# Memory.net
KiCad netlist of a schematic drawn in Altium Designer
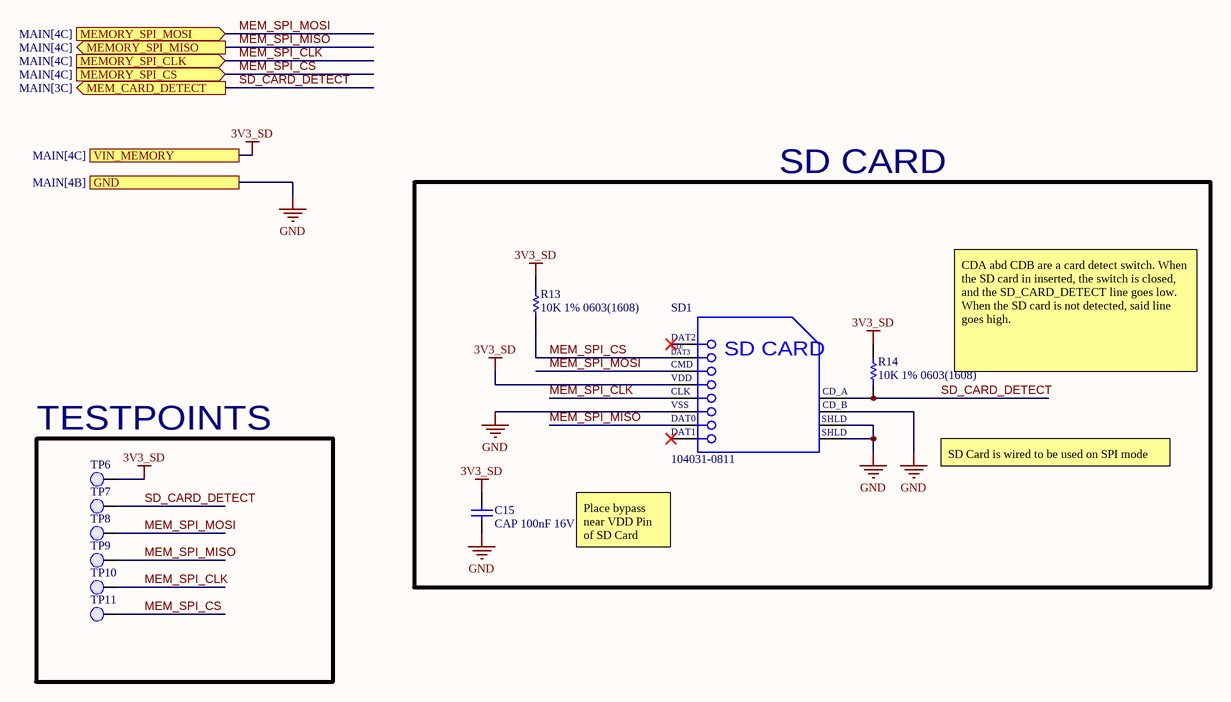
[diagram p0: Memory.SchDoc]

(export (version "E")
  (design (tool "Eeschema 10.0.6"))
  (components
    (comp (ref "C15")
      (value "CAP 100nF 16V 0603(1608)")
      (footprint "CAPC0603(1608)100_N")
      (description "CAP 100nF 16V ±10% 0603 (1608 Metric) Thickness 1mm SMD")
      (fields (field (name "TOLERANCE") "Â±10%"))
      (libsource (lib "Altium Content Vault") (part "CAP"))
    )
    (comp (ref "R13")
      (value "10K 1% 0603(1608)")
      (footprint "RESC0603(1608)_N")
      (description "10K 0.1W 1% 0603 (1608 Metric)  SMD")
      (fields (field (name "POWER") "0.1 W") (field (name "TOLERANCE") "1 %"))
      (libsource (lib "Altium Content Vault") (part "RES"))
    )
    (comp (ref "R14")
      (value "10K 1% 0603(1608)")
      (footprint "RESC0603(1608)_N")
      (description "10K 0.1W 1% 0603 (1608 Metric)  SMD")
      (fields (field (name "POWER") "0.1 W") (field (name "TOLERANCE") "1 %"))
      (libsource (lib "Altium Content Vault") (part "RES"))
    )
    (comp (ref "SD1")
      (value "104031-0811")
      (footprint "MOLX-104031-0811_V")
      (description "Micro SD Card, RA, -25 to 85 degC, 8-Pin SMD, RoHS, Tape and Reel")
      (fields (field (name "MANUFACTURER") "Molex"))
      (libsource (lib "Altium Content Vault") (part "CN-SD-8-2SW-2S"))
    )
    (comp (ref "TP6")
      (value "0.1\" Pad")
      (footprint "PCBComponent")
      (libsource (lib "Components - 12.02.20 - 18.05") (part "0.1{dblquote} Pad-A.4"))
    )
    (comp (ref "TP7")
      (value "0.1\" Pad")
      (footprint "PCBComponent")
      (libsource (lib "Components - 12.02.20 - 18.05") (part "0.1{dblquote} Pad-A.4"))
    )
    (comp (ref "TP8")
      (value "0.1\" Pad")
      (footprint "PCBComponent")
      (libsource (lib "Components - 12.02.20 - 18.05") (part "0.1{dblquote} Pad-A.4"))
    )
    (comp (ref "TP9")
      (value "0.1\" Pad")
      (footprint "PCBComponent")
      (libsource (lib "Components - 12.02.20 - 18.05") (part "0.1{dblquote} Pad-A.4"))
    )
    (comp (ref "TP10")
      (value "0.1\" Pad")
      (footprint "PCBComponent")
      (libsource (lib "Components - 12.02.20 - 18.05") (part "0.1{dblquote} Pad-A.4"))
    )
    (comp (ref "TP11")
      (value "0.1\" Pad")
      (footprint "PCBComponent")
      (libsource (lib "Components - 12.02.20 - 18.05") (part "0.1{dblquote} Pad-A.4"))
    )
  )
  (nets
    (net (code "1") (name "/MEM_SPI_CLK") (class "Default")
      (node (ref "SD1") (pin "5") (pinfunction "CLK_5") (pintype "passive"))
      (node (ref "TP10") (pin "1") (pinfunction "PAD_1") (pintype "passive"))
    )
    (net (code "2") (name "/MEM_SPI_CS") (class "Default")
      (node (ref "R13") (pin "1") (pinfunction "1_1") (pintype "passive"))
      (node (ref "SD1") (pin "2") (pinfunction "CMD_2") (pintype "passive"))
      (node (ref "TP11") (pin "1") (pinfunction "PAD_1") (pintype "passive"))
    )
    (net (code "3") (name "/MEM_SPI_MISO") (class "Default")
      (node (ref "SD1") (pin "7") (pinfunction "DAT0_7") (pintype "passive"))
      (node (ref "TP9") (pin "1") (pinfunction "PAD_1") (pintype "passive"))
    )
    (net (code "4") (name "/MEM_SPI_MOSI") (class "Default")
      (node (ref "SD1") (pin "3") (pinfunction "VSS1_3") (pintype "passive"))
      (node (ref "TP8") (pin "1") (pinfunction "PAD_1") (pintype "passive"))
    )
    (net (code "5") (name "/SD_CARD_DETECT") (class "Default")
      (node (ref "R14") (pin "1") (pinfunction "1_1") (pintype "passive"))
      (node (ref "SD1") (pin "9") (pinfunction "CD_A_9") (pintype "passive"))
      (node (ref "TP7") (pin "1") (pinfunction "PAD_1") (pintype "passive"))
    )
    (net (code "6") (name "3V3_SD") (class "Default")
      (node (ref "C15") (pin "2") (pinfunction "2_2") (pintype "passive"))
      (node (ref "R13") (pin "2") (pinfunction "2_2") (pintype "passive"))
      (node (ref "R14") (pin "2") (pinfunction "2_2") (pintype "passive"))
      (node (ref "SD1") (pin "4") (pinfunction "VDD_4") (pintype "passive"))
      (node (ref "TP6") (pin "1") (pinfunction "PAD_1") (pintype "passive"))
    )
    (net (code "7") (name "GND") (class "Default")
      (node (ref "C15") (pin "1") (pinfunction "1_1") (pintype "passive"))
      (node (ref "SD1") (pin "10") (pinfunction "CD_B_10") (pintype "passive"))
      (node (ref "SD1") (pin "11") (pinfunction "SHLD1_11") (pintype "passive"))
      (node (ref "SD1") (pin "12") (pinfunction "SHLD2_12") (pintype "passive"))
      (node (ref "SD1") (pin "6") (pinfunction "VSS2_6") (pintype "passive"))
    )
    (net (code "8") (name "unconnected-(SD1-CD{slash}DAT3-Pad1)") (class "Default")
      (node (ref "SD1") (pin "1") (pinfunction "CD/DAT3_1") (pintype "passive+no_connect"))
    )
    (net (code "9") (name "unconnected-(SD1-DAT1-Pad8)") (class "Default")
      (node (ref "SD1") (pin "8") (pinfunction "DAT1_8") (pintype "passive+no_connect"))
    )
  )
)
